# connect_4.net
KiCad netlist of a schematic drawn in EasyEDA
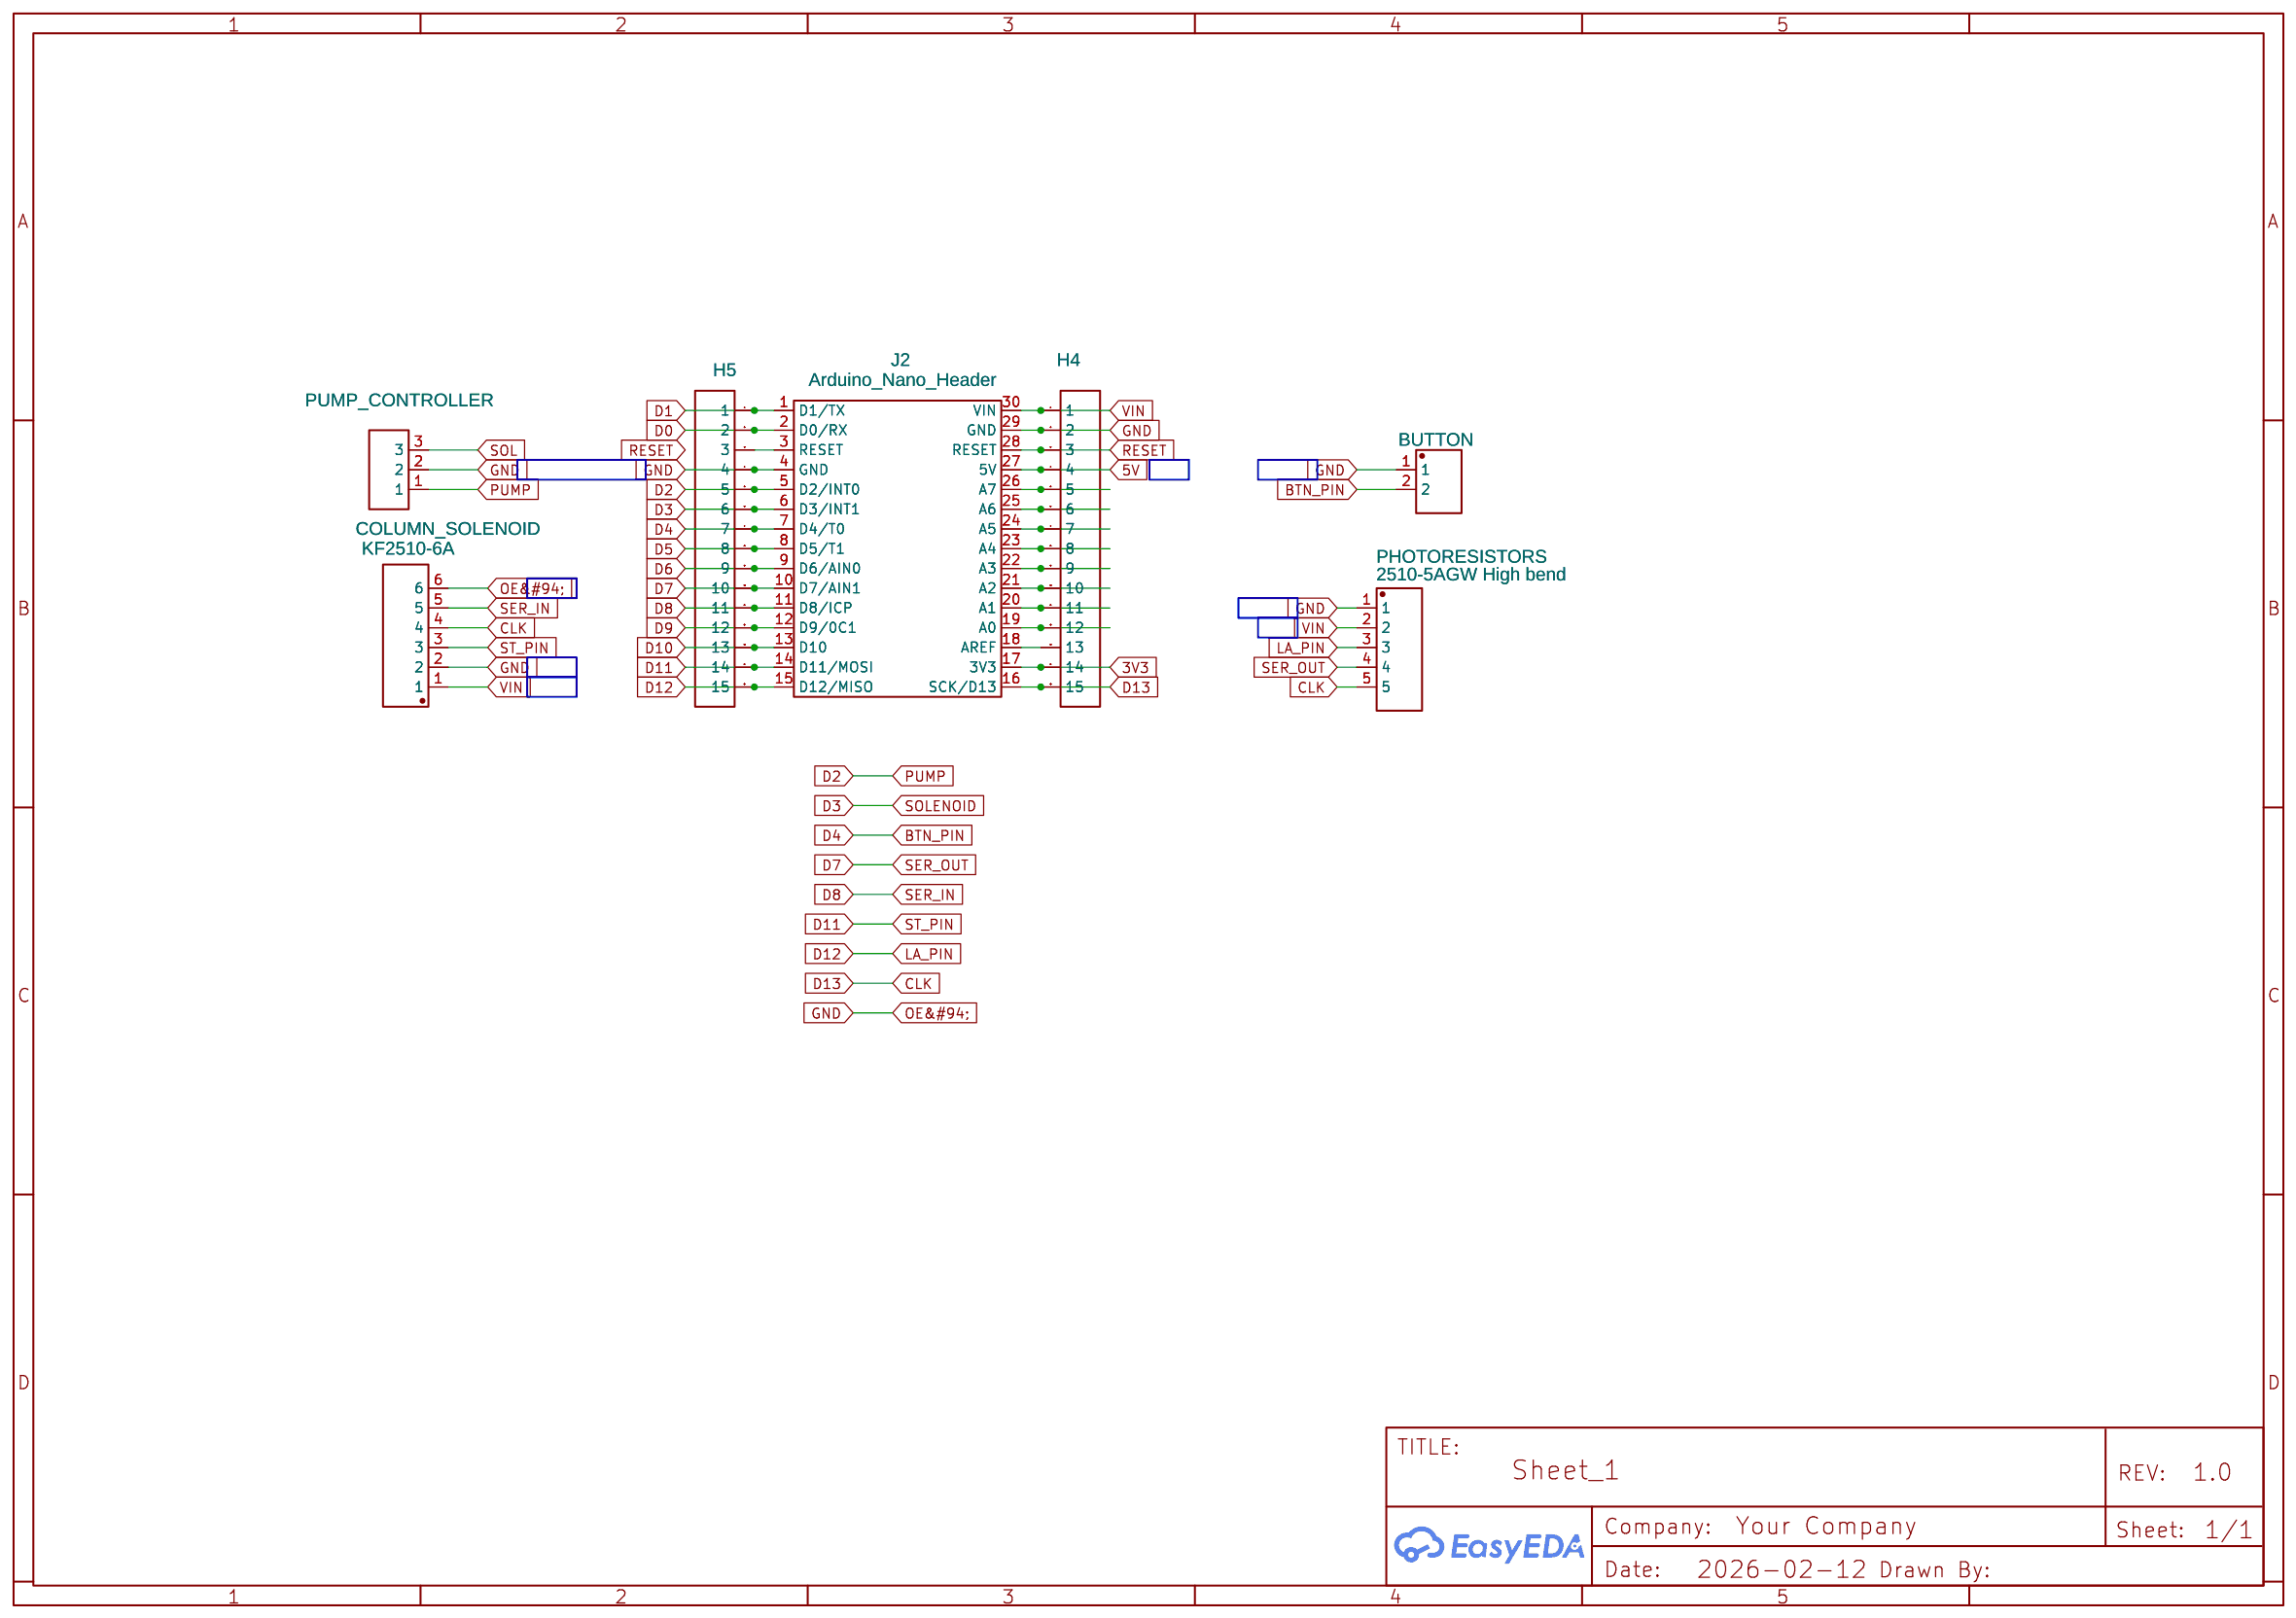
[diagram p0: schematic sheet]

(export (version "E")
  (design (tool "Eeschema 10.0.6"))
  (components
    (comp (ref "COLUMN_SOLENOID")
      (value "KF2510-6A")
      (fields (field (name "Manufacturer Part") "KF2510-6A针座"))
      (libsource (lib "") (part "KF2510-6A"))
    )
    (comp (ref "D3")
      (value "BUTTON")
      (fields (field (name "Manufacturer Part") "KF2510-2A") (field (name "Manufacturer") "BOOMELE"))
      (libsource (lib "") (part "KF2510-2A"))
    )
    (comp (ref "H4") (value "HDR-F-2.54_1x15") (libsource (lib "") (part "HDR-F-2.54_1x15")))
    (comp (ref "H5") (value "HDR-F-2.54_1x15") (libsource (lib "") (part "HDR-F-2.54_1x15_1")))
    (comp (ref "J2") (value "Arduino_Nano_Header") (libsource (lib "") (part "Arduino_Nano_Header")))
    (comp (ref "PHOTORESISTORS")
      (value "2510-5AGW High bend")
      (fields (field (name "Manufacturer Part") "2510-5A高弯") (field (name "Manufacturer") "BOOMELE(博穆精密)"))
      (libsource (lib "") (part "2510-5AGW High bend"))
    )
    (comp (ref "PUMP_CONTROLLER") (value "FK2510") (libsource (lib "") (part "kf2510_3A")))
  )
  (nets
    (net (code "1") (name "3V3") (class "Default")
      (node (ref "H4") (pin "14") (pinfunction "14_14") (pintype "unspecified"))
      (node (ref "J2") (pin "17") (pinfunction "3V3_17") (pintype "unspecified"))
    )
    (net (code "2") (name "5V") (class "Default")
      (node (ref "H4") (pin "4") (pinfunction "4_4") (pintype "unspecified"))
      (node (ref "J2") (pin "27") (pinfunction "5V_27") (pintype "unspecified"))
    )
    (net (code "3") (name "BTN_PIN") (class "Default")
      (node (ref "D3") (pin "2") (pinfunction "2_2") (pintype "unspecified"))
      (node (ref "H5") (pin "7") (pinfunction "7_7") (pintype "unspecified"))
      (node (ref "J2") (pin "7") (pinfunction "D4/T0_7") (pintype "unspecified"))
    )
    (net (code "4") (name "CLK") (class "Default")
      (node (ref "COLUMN_SOLENOID") (pin "4") (pinfunction "4_4") (pintype "unspecified"))
      (node (ref "H4") (pin "15") (pinfunction "15_15") (pintype "unspecified"))
      (node (ref "J2") (pin "16") (pinfunction "SCK/D13_16") (pintype "unspecified"))
      (node (ref "PHOTORESISTORS") (pin "5") (pinfunction "5_5") (pintype "unspecified"))
    )
    (net (code "5") (name "D0") (class "Default")
      (node (ref "H5") (pin "2") (pinfunction "2_2") (pintype "unspecified"))
      (node (ref "J2") (pin "2") (pinfunction "D0/RX_2") (pintype "unspecified"))
    )
    (net (code "6") (name "D1") (class "Default")
      (node (ref "H5") (pin "1") (pinfunction "1_1") (pintype "unspecified"))
      (node (ref "J2") (pin "1") (pinfunction "D1/TX_1") (pintype "unspecified"))
    )
    (net (code "7") (name "D2") (class "Default")
      (node (ref "H5") (pin "5") (pinfunction "5_5") (pintype "unspecified"))
      (node (ref "J2") (pin "5") (pinfunction "D2/INT0_5") (pintype "unspecified"))
      (node (ref "PUMP_CONTROLLER") (pin "1") (pinfunction "1_1") (pintype "unspecified"))
    )
    (net (code "8") (name "D3") (class "Default")
      (node (ref "H5") (pin "6") (pinfunction "6_6") (pintype "unspecified"))
      (node (ref "J2") (pin "6") (pinfunction "D3/INT1_6") (pintype "unspecified"))
    )
    (net (code "9") (name "D5") (class "Default")
      (node (ref "H5") (pin "8") (pinfunction "8_8") (pintype "unspecified"))
      (node (ref "J2") (pin "8") (pinfunction "D5/T1_8") (pintype "unspecified"))
    )
    (net (code "10") (name "D6") (class "Default")
      (node (ref "H5") (pin "9") (pinfunction "9_9") (pintype "unspecified"))
      (node (ref "J2") (pin "9") (pinfunction "D6/AIN0_9") (pintype "unspecified"))
    )
    (net (code "11") (name "D7") (class "Default")
      (node (ref "H5") (pin "10") (pinfunction "10_10") (pintype "unspecified"))
      (node (ref "J2") (pin "10") (pinfunction "D7/AIN1_10") (pintype "unspecified"))
      (node (ref "PHOTORESISTORS") (pin "4") (pinfunction "4_4") (pintype "unspecified"))
    )
    (net (code "12") (name "D8") (class "Default")
      (node (ref "COLUMN_SOLENOID") (pin "5") (pinfunction "5_5") (pintype "unspecified"))
      (node (ref "H5") (pin "11") (pinfunction "11_11") (pintype "unspecified"))
      (node (ref "J2") (pin "11") (pinfunction "D8/ICP_11") (pintype "unspecified"))
    )
    (net (code "13") (name "D9") (class "Default")
      (node (ref "H5") (pin "12") (pinfunction "12_12") (pintype "unspecified"))
      (node (ref "J2") (pin "12") (pinfunction "D9/0C1_12") (pintype "unspecified"))
    )
    (net (code "14") (name "D10") (class "Default")
      (node (ref "H5") (pin "13") (pinfunction "13_13") (pintype "unspecified"))
      (node (ref "J2") (pin "13") (pinfunction "D10_13") (pintype "unspecified"))
    )
    (net (code "15") (name "D11") (class "Default")
      (node (ref "COLUMN_SOLENOID") (pin "3") (pinfunction "3_3") (pintype "unspecified"))
      (node (ref "H5") (pin "14") (pinfunction "14_14") (pintype "unspecified"))
      (node (ref "J2") (pin "14") (pinfunction "D11/MOSI_14") (pintype "unspecified"))
    )
    (net (code "16") (name "D12") (class "Default")
      (node (ref "H5") (pin "15") (pinfunction "15_15") (pintype "unspecified"))
      (node (ref "J2") (pin "15") (pinfunction "D12/MISO_15") (pintype "unspecified"))
      (node (ref "PHOTORESISTORS") (pin "3") (pinfunction "3_3") (pintype "unspecified"))
    )
    (net (code "17") (name "GND") (class "Default")
      (node (ref "COLUMN_SOLENOID") (pin "2") (pinfunction "2_2") (pintype "unspecified"))
      (node (ref "COLUMN_SOLENOID") (pin "6") (pinfunction "6_6") (pintype "unspecified"))
      (node (ref "D3") (pin "1") (pinfunction "1_1") (pintype "unspecified"))
      (node (ref "H4") (pin "2") (pinfunction "2_2") (pintype "unspecified"))
      (node (ref "H5") (pin "4") (pinfunction "4_4") (pintype "unspecified"))
      (node (ref "J2") (pin "29") (pinfunction "GND_29") (pintype "unspecified"))
      (node (ref "J2") (pin "4") (pinfunction "GND_4") (pintype "unspecified"))
      (node (ref "PHOTORESISTORS") (pin "1") (pinfunction "1_1") (pintype "unspecified"))
      (node (ref "PUMP_CONTROLLER") (pin "2") (pinfunction "2_2") (pintype "unspecified"))
    )
    (net (code "18") (name "Net-(H5-Pad3)") (class "Default")
      (node (ref "H5") (pin "3") (pinfunction "3_3") (pintype "unspecified"))
      (node (ref "J2") (pin "3") (pinfunction "RESET_3") (pintype "unspecified"))
    )
    (net (code "19") (name "Net-(J2-A0)") (class "Default")
      (node (ref "H4") (pin "12") (pinfunction "12_12") (pintype "unspecified"))
      (node (ref "J2") (pin "19") (pinfunction "A0_19") (pintype "unspecified"))
    )
    (net (code "20") (name "Net-(J2-A1)") (class "Default")
      (node (ref "H4") (pin "11") (pinfunction "11_11") (pintype "unspecified"))
      (node (ref "J2") (pin "20") (pinfunction "A1_20") (pintype "unspecified"))
    )
    (net (code "21") (name "Net-(J2-A2)") (class "Default")
      (node (ref "H4") (pin "10") (pinfunction "10_10") (pintype "unspecified"))
      (node (ref "J2") (pin "21") (pinfunction "A2_21") (pintype "unspecified"))
    )
    (net (code "22") (name "Net-(J2-A3)") (class "Default")
      (node (ref "H4") (pin "9") (pinfunction "9_9") (pintype "unspecified"))
      (node (ref "J2") (pin "22") (pinfunction "A3_22") (pintype "unspecified"))
    )
    (net (code "23") (name "Net-(J2-A4)") (class "Default")
      (node (ref "H4") (pin "8") (pinfunction "8_8") (pintype "unspecified"))
      (node (ref "J2") (pin "23") (pinfunction "A4_23") (pintype "unspecified"))
    )
    (net (code "24") (name "Net-(J2-A5)") (class "Default")
      (node (ref "H4") (pin "7") (pinfunction "7_7") (pintype "unspecified"))
      (node (ref "J2") (pin "24") (pinfunction "A5_24") (pintype "unspecified"))
    )
    (net (code "25") (name "Net-(J2-A6)") (class "Default")
      (node (ref "H4") (pin "6") (pinfunction "6_6") (pintype "unspecified"))
      (node (ref "J2") (pin "25") (pinfunction "A6_25") (pintype "unspecified"))
    )
    (net (code "26") (name "Net-(J2-A7)") (class "Default")
      (node (ref "H4") (pin "5") (pinfunction "5_5") (pintype "unspecified"))
      (node (ref "J2") (pin "26") (pinfunction "A7_26") (pintype "unspecified"))
    )
    (net (code "27") (name "Net-(J2-AREF)") (class "Default")
      (node (ref "H4") (pin "13") (pinfunction "13_13") (pintype "unspecified"))
      (node (ref "J2") (pin "18") (pinfunction "AREF_18") (pintype "unspecified"))
    )
    (net (code "28") (name "RESET") (class "Default")
      (node (ref "H4") (pin "3") (pinfunction "3_3") (pintype "unspecified"))
      (node (ref "J2") (pin "28") (pinfunction "RESET_28") (pintype "unspecified"))
    )
    (net (code "29") (name "SOL") (class "Default")
      (node (ref "PUMP_CONTROLLER") (pin "3") (pinfunction "3_3") (pintype "unspecified"))
    )
    (net (code "30") (name "VIN") (class "Default")
      (node (ref "COLUMN_SOLENOID") (pin "1") (pinfunction "1_1") (pintype "unspecified"))
      (node (ref "H4") (pin "1") (pinfunction "1_1") (pintype "unspecified"))
      (node (ref "J2") (pin "30") (pinfunction "VIN_30") (pintype "unspecified"))
      (node (ref "PHOTORESISTORS") (pin "2") (pinfunction "2_2") (pintype "unspecified"))
    )
  )
)
